# Nivel_superior.net
KiCad netlist of a schematic drawn in EAGLE
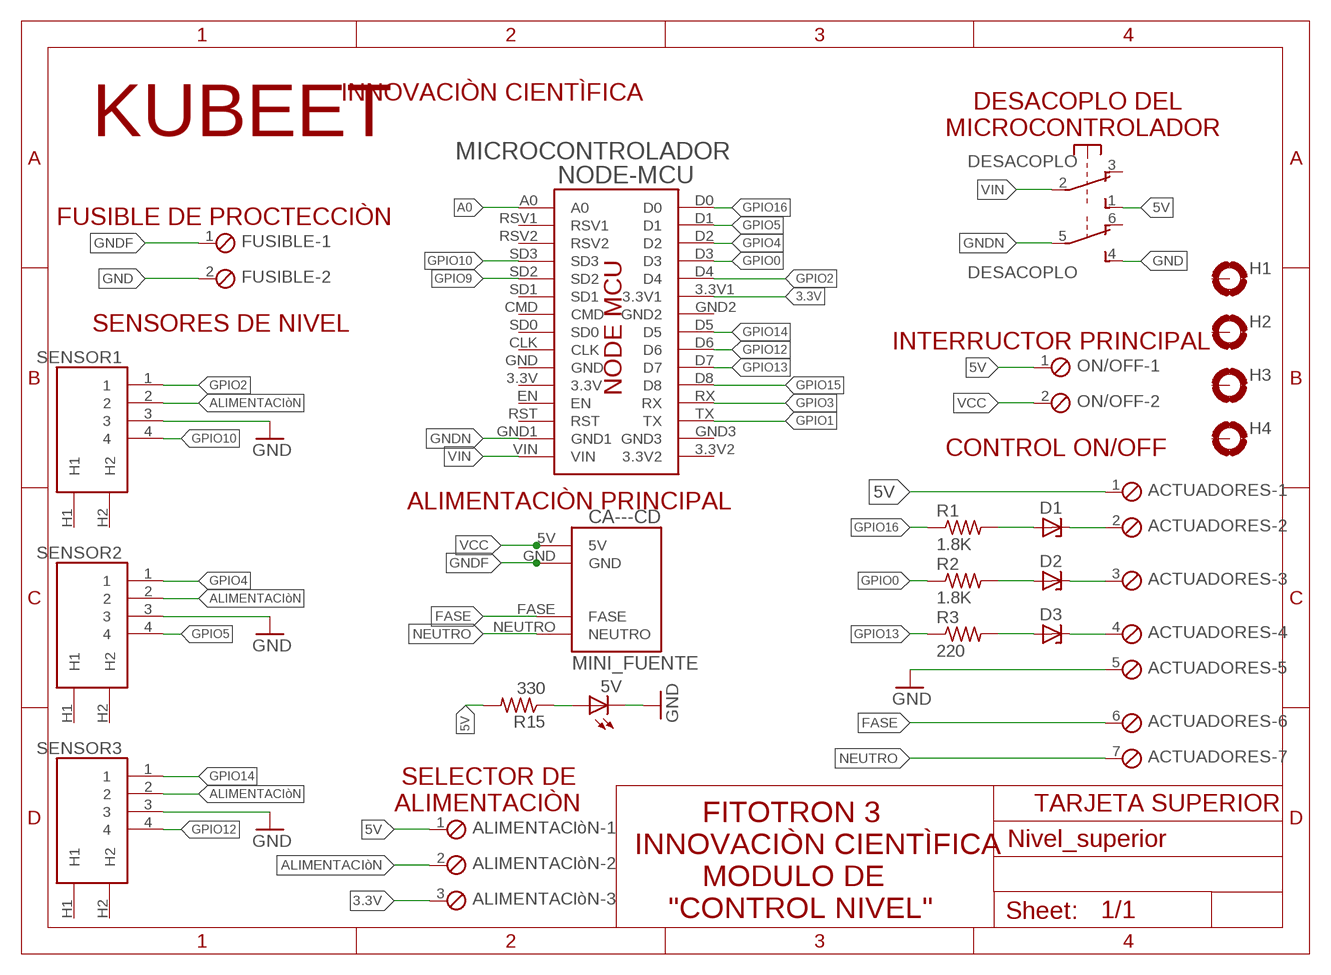
[diagram p0: schematic, sheet 1]

(export (version "E")
  (design (tool "Eeschema 10.0.6"))
  (components
    (comp (ref "5V")
      (value "LED5MM")
      (footprint "eagle-import:LED5MM")
      (libsource (lib "eagle-import") (part "LED5MM"))
    )
    (comp (ref "ACTUADORES")
      (value "MPT7")
      (footprint "eagle-import:7POL254")
      (libsource (lib "eagle-import") (part "MPT7"))
    )
    (comp (ref "ALIMENTACIòN")
      (value "MPT3")
      (footprint "eagle-import:3POL254")
      (libsource (lib "eagle-import") (part "MPT3"))
    )
    (comp (ref "CA---CD")
      (value "MINI_FUENTE")
      (footprint "eagle-import:MINI_FUENTE2")
      (libsource (lib "eagle-import") (part "MINI_FUENTE2"))
    )
    (comp (ref "D1")
      (value "1N821")
      (footprint "eagle-import:DO35Z10")
      (libsource (lib "eagle-import") (part "1N821"))
    )
    (comp (ref "D2")
      (value "1N821")
      (footprint "eagle-import:DO35Z10")
      (libsource (lib "eagle-import") (part "1N821"))
    )
    (comp (ref "D3")
      (value "1N821")
      (footprint "eagle-import:DO35Z10")
      (libsource (lib "eagle-import") (part "1N821"))
    )
    (comp (ref "DESACOPLO")
      (value "9077-2")
      (footprint "eagle-import:9077-2")
      (libsource (lib "eagle-import") (part "9077-2"))
    )
    (comp (ref "FUSIBLE")
      (value "MPT2")
      (footprint "eagle-import:2POL254")
      (libsource (lib "eagle-import") (part "MPT2"))
    )
    (comp (ref "H1")
      (value "MOUNT-PAD-ROUND3.6")
      (footprint "eagle-import:3,6-PAD")
      (libsource (lib "eagle-import") (part "MOUNT-PAD-ROUND3.6"))
    )
    (comp (ref "H2")
      (value "MOUNT-PAD-ROUND3.6")
      (footprint "eagle-import:3,6-PAD")
      (libsource (lib "eagle-import") (part "MOUNT-PAD-ROUND3.6"))
    )
    (comp (ref "H3")
      (value "MOUNT-PAD-ROUND3.6")
      (footprint "eagle-import:3,6-PAD")
      (libsource (lib "eagle-import") (part "MOUNT-PAD-ROUND3.6"))
    )
    (comp (ref "H4")
      (value "MOUNT-PAD-ROUND3.6")
      (footprint "eagle-import:3,6-PAD")
      (libsource (lib "eagle-import") (part "MOUNT-PAD-ROUND3.6"))
    )
    (comp (ref "MICROCONTROLADOR")
      (value "NODE-MCU")
      (footprint "eagle-import:NODE-MCU")
      (libsource (lib "eagle-import") (part "NODE-MCU"))
    )
    (comp (ref "ON/OFF")
      (value "MPT2")
      (footprint "eagle-import:2POL254")
      (libsource (lib "eagle-import") (part "MPT2"))
    )
    (comp (ref "R1")
      (value "1.8K")
      (footprint "eagle-import:0207_7")
      (libsource (lib "eagle-import") (part "R-US_0207/7"))
    )
    (comp (ref "R2")
      (value "1.8K")
      (footprint "eagle-import:0207_7")
      (libsource (lib "eagle-import") (part "R-US_0207/7"))
    )
    (comp (ref "R3")
      (value "220")
      (footprint "eagle-import:0207_7")
      (libsource (lib "eagle-import") (part "R-US_0207/7"))
    )
    (comp (ref "R15")
      (value "330")
      (footprint "eagle-import:0207_7")
      (libsource (lib "eagle-import") (part "R-US_0207/7"))
    )
    (comp (ref "SENSOR1")
      (value "RJ11")
      (footprint "eagle-import:RJ11")
      (libsource (lib "eagle-import") (part "RJ11"))
    )
    (comp (ref "SENSOR2")
      (value "RJ11")
      (footprint "eagle-import:RJ11")
      (libsource (lib "eagle-import") (part "RJ11"))
    )
    (comp (ref "SENSOR3")
      (value "RJ11")
      (footprint "eagle-import:RJ11")
      (libsource (lib "eagle-import") (part "RJ11"))
    )
  )
  (nets
    (net (code "1") (name "3.3V") (class "Default")
      (node (ref "ALIMENTACIòN") (pin "3") (pinfunction "1_3") (pintype "passive"))
      (node (ref "MICROCONTROLADOR") (pin "3.3V1") (pinfunction "3.3V1_3.3V1") (pintype "bidirectional"))
    )
    (net (code "2") (name "5V") (class "Default")
      (node (ref "ACTUADORES") (pin "1") (pinfunction "1_1") (pintype "passive"))
      (node (ref "ALIMENTACIòN") (pin "1") (pinfunction "1_1") (pintype "passive"))
      (node (ref "DESACOPLO") (pin "1") (pinfunction "S_1") (pintype "passive"))
      (node (ref "ON/OFF") (pin "1") (pinfunction "1_1") (pintype "passive"))
      (node (ref "R15") (pin "2") (pinfunction "2_2") (pintype "passive"))
    )
    (net (code "3") (name "A0") (class "Default")
      (node (ref "MICROCONTROLADOR") (pin "A0") (pinfunction "A0_A0") (pintype "bidirectional"))
    )
    (net (code "4") (name "ALIMENTACIòN") (class "Default")
      (node (ref "ALIMENTACIòN") (pin "2") (pinfunction "1_2") (pintype "passive"))
      (node (ref "SENSOR1") (pin "2") (pinfunction "2_2") (pintype "bidirectional"))
      (node (ref "SENSOR2") (pin "2") (pinfunction "2_2") (pintype "bidirectional"))
      (node (ref "SENSOR3") (pin "2") (pinfunction "2_2") (pintype "bidirectional"))
    )
    (net (code "5") (name "FASE") (class "Default")
      (node (ref "ACTUADORES") (pin "6") (pinfunction "1_6") (pintype "passive"))
      (node (ref "CA---CD") (pin "FASE") (pinfunction "FASE_FASE") (pintype "bidirectional"))
    )
    (net (code "6") (name "GND") (class "Default")
      (node (ref "5V") (pin "K") (pinfunction "C_K") (pintype "passive"))
      (node (ref "ACTUADORES") (pin "5") (pinfunction "1_5") (pintype "passive"))
      (node (ref "DESACOPLO") (pin "4") (pinfunction "S_4") (pintype "passive"))
      (node (ref "FUSIBLE") (pin "2") (pinfunction "1_2") (pintype "passive"))
      (node (ref "SENSOR1") (pin "3") (pinfunction "3_3") (pintype "bidirectional"))
      (node (ref "SENSOR2") (pin "3") (pinfunction "3_3") (pintype "bidirectional"))
      (node (ref "SENSOR3") (pin "3") (pinfunction "3_3") (pintype "bidirectional"))
    )
    (net (code "7") (name "GNDF") (class "Default")
      (node (ref "CA---CD") (pin "GND") (pinfunction "GND_GND") (pintype "bidirectional"))
      (node (ref "FUSIBLE") (pin "1") (pinfunction "1_1") (pintype "passive"))
    )
    (net (code "8") (name "GNDN") (class "Default")
      (node (ref "DESACOPLO") (pin "5") (pinfunction "P_5") (pintype "passive"))
      (node (ref "MICROCONTROLADOR") (pin "GND1") (pinfunction "GND1_GND1") (pintype "bidirectional"))
    )
    (net (code "9") (name "GPIO0") (class "Default")
      (node (ref "MICROCONTROLADOR") (pin "D3") (pinfunction "D3_D3") (pintype "bidirectional"))
      (node (ref "R2") (pin "1") (pinfunction "1_1") (pintype "passive"))
    )
    (net (code "10") (name "GPIO1") (class "Default")
      (node (ref "MICROCONTROLADOR") (pin "TX") (pinfunction "TX_TX") (pintype "bidirectional"))
    )
    (net (code "11") (name "GPIO2") (class "Default")
      (node (ref "MICROCONTROLADOR") (pin "D4") (pinfunction "D4_D4") (pintype "bidirectional"))
      (node (ref "SENSOR1") (pin "1") (pinfunction "1_1") (pintype "bidirectional"))
    )
    (net (code "12") (name "GPIO3") (class "Default")
      (node (ref "MICROCONTROLADOR") (pin "RX") (pinfunction "RX_RX") (pintype "bidirectional"))
    )
    (net (code "13") (name "GPIO4") (class "Default")
      (node (ref "MICROCONTROLADOR") (pin "D2") (pinfunction "D2_D2") (pintype "bidirectional"))
      (node (ref "SENSOR2") (pin "1") (pinfunction "1_1") (pintype "bidirectional"))
    )
    (net (code "14") (name "GPIO5") (class "Default")
      (node (ref "MICROCONTROLADOR") (pin "D1") (pinfunction "D1_D1") (pintype "bidirectional"))
      (node (ref "SENSOR2") (pin "4") (pinfunction "4_4") (pintype "bidirectional"))
    )
    (net (code "15") (name "GPIO9") (class "Default")
      (node (ref "MICROCONTROLADOR") (pin "SD2") (pinfunction "SD2_SD2") (pintype "bidirectional"))
    )
    (net (code "16") (name "GPIO10") (class "Default")
      (node (ref "MICROCONTROLADOR") (pin "SD3") (pinfunction "SD3_SD3") (pintype "bidirectional"))
      (node (ref "SENSOR1") (pin "4") (pinfunction "4_4") (pintype "bidirectional"))
    )
    (net (code "17") (name "GPIO12") (class "Default")
      (node (ref "MICROCONTROLADOR") (pin "D6") (pinfunction "D6_D6") (pintype "bidirectional"))
      (node (ref "SENSOR3") (pin "4") (pinfunction "4_4") (pintype "bidirectional"))
    )
    (net (code "18") (name "GPIO13") (class "Default")
      (node (ref "MICROCONTROLADOR") (pin "D7") (pinfunction "D7_D7") (pintype "bidirectional"))
      (node (ref "R3") (pin "1") (pinfunction "1_1") (pintype "passive"))
    )
    (net (code "19") (name "GPIO14") (class "Default")
      (node (ref "MICROCONTROLADOR") (pin "D5") (pinfunction "D5_D5") (pintype "bidirectional"))
      (node (ref "SENSOR3") (pin "1") (pinfunction "1_1") (pintype "bidirectional"))
    )
    (net (code "20") (name "GPIO15") (class "Default")
      (node (ref "MICROCONTROLADOR") (pin "D8") (pinfunction "D8_D8") (pintype "bidirectional"))
    )
    (net (code "21") (name "GPIO16") (class "Default")
      (node (ref "MICROCONTROLADOR") (pin "D0") (pinfunction "D0_D0") (pintype "bidirectional"))
      (node (ref "R1") (pin "1") (pinfunction "1_1") (pintype "passive"))
    )
    (net (code "22") (name "NEUTRO") (class "Default")
      (node (ref "ACTUADORES") (pin "7") (pinfunction "1_7") (pintype "passive"))
      (node (ref "CA---CD") (pin "NEUTRO") (pinfunction "NEUTRO_NEUTRO") (pintype "bidirectional"))
    )
    (net (code "23") (name "Net-(5V-PadA)") (class "Default")
      (node (ref "5V") (pin "A") (pinfunction "A_A") (pintype "passive"))
      (node (ref "R15") (pin "1") (pinfunction "1_1") (pintype "passive"))
    )
    (net (code "24") (name "Net-(ACTUADORESB-1)") (class "Default")
      (node (ref "ACTUADORES") (pin "2") (pinfunction "1_2") (pintype "passive"))
      (node (ref "D1") (pin "C") (pinfunction "C_C") (pintype "passive"))
    )
    (net (code "25") (name "Net-(ACTUADORESC-1)") (class "Default")
      (node (ref "ACTUADORES") (pin "3") (pinfunction "1_3") (pintype "passive"))
      (node (ref "D2") (pin "C") (pinfunction "C_C") (pintype "passive"))
    )
    (net (code "26") (name "Net-(ACTUADORESD-1)") (class "Default")
      (node (ref "ACTUADORES") (pin "4") (pinfunction "1_4") (pintype "passive"))
      (node (ref "D3") (pin "C") (pinfunction "C_C") (pintype "passive"))
    )
    (net (code "27") (name "Net-(D1-PadA)") (class "Default")
      (node (ref "D1") (pin "A") (pinfunction "A_A") (pintype "passive"))
      (node (ref "R1") (pin "2") (pinfunction "2_2") (pintype "passive"))
    )
    (net (code "28") (name "Net-(D2-PadA)") (class "Default")
      (node (ref "D2") (pin "A") (pinfunction "A_A") (pintype "passive"))
      (node (ref "R2") (pin "2") (pinfunction "2_2") (pintype "passive"))
    )
    (net (code "29") (name "Net-(D3-PadA)") (class "Default")
      (node (ref "D3") (pin "A") (pinfunction "A_A") (pintype "passive"))
      (node (ref "R3") (pin "2") (pinfunction "2_2") (pintype "passive"))
    )
    (net (code "30") (name "VCC") (class "Default")
      (node (ref "CA---CD") (pin "5V") (pinfunction "5V_5V") (pintype "bidirectional"))
      (node (ref "ON/OFF") (pin "2") (pinfunction "1_2") (pintype "passive"))
    )
    (net (code "31") (name "VIN") (class "Default")
      (node (ref "DESACOPLO") (pin "2") (pinfunction "P_2") (pintype "passive"))
      (node (ref "MICROCONTROLADOR") (pin "VIN") (pinfunction "VIN_VIN") (pintype "bidirectional"))
    )
    (net (code "32") (name "unconnected-(DESACOPLOA-O-Pad3)") (class "Default")
      (node (ref "DESACOPLO") (pin "3") (pinfunction "O_3") (pintype "passive"))
    )
    (net (code "33") (name "unconnected-(DESACOPLOB-O-Pad6)") (class "Default")
      (node (ref "DESACOPLO") (pin "6") (pinfunction "O_6") (pintype "passive"))
    )
    (net (code "34") (name "unconnected-(H1-MOUNT-PadB3,6)") (class "Default")
      (node (ref "H1") (pin "B3,6") (pinfunction "MOUNT_B3,6") (pintype "passive"))
    )
    (net (code "35") (name "unconnected-(H2-MOUNT-PadB3,6)") (class "Default")
      (node (ref "H2") (pin "B3,6") (pinfunction "MOUNT_B3,6") (pintype "passive"))
    )
    (net (code "36") (name "unconnected-(H3-MOUNT-PadB3,6)") (class "Default")
      (node (ref "H3") (pin "B3,6") (pinfunction "MOUNT_B3,6") (pintype "passive"))
    )
    (net (code "37") (name "unconnected-(H4-MOUNT-PadB3,6)") (class "Default")
      (node (ref "H4") (pin "B3,6") (pinfunction "MOUNT_B3,6") (pintype "passive"))
    )
    (net (code "38") (name "unconnected-(MICROCONTROLADOR-Pad3.3V)") (class "Default")
      (node (ref "MICROCONTROLADOR") (pin "3.3V") (pinfunction "3.3V_3.3V") (pintype "bidirectional"))
    )
    (net (code "39") (name "unconnected-(MICROCONTROLADOR-Pad3.3V2)") (class "Default")
      (node (ref "MICROCONTROLADOR") (pin "3.3V2") (pinfunction "3.3V2_3.3V2") (pintype "bidirectional"))
    )
    (net (code "40") (name "unconnected-(MICROCONTROLADOR-PadCLK)") (class "Default")
      (node (ref "MICROCONTROLADOR") (pin "CLK") (pinfunction "CLK_CLK") (pintype "bidirectional"))
    )
    (net (code "41") (name "unconnected-(MICROCONTROLADOR-PadCMD)") (class "Default")
      (node (ref "MICROCONTROLADOR") (pin "CMD") (pinfunction "CMD_CMD") (pintype "bidirectional"))
    )
    (net (code "42") (name "unconnected-(MICROCONTROLADOR-PadEN)") (class "Default")
      (node (ref "MICROCONTROLADOR") (pin "EN") (pinfunction "EN_EN") (pintype "bidirectional"))
    )
    (net (code "43") (name "unconnected-(MICROCONTROLADOR-PadGND)") (class "Default")
      (node (ref "MICROCONTROLADOR") (pin "GND") (pinfunction "GND_GND") (pintype "bidirectional"))
    )
    (net (code "44") (name "unconnected-(MICROCONTROLADOR-PadGND2)") (class "Default")
      (node (ref "MICROCONTROLADOR") (pin "GND2") (pinfunction "GND2_GND2") (pintype "bidirectional"))
    )
    (net (code "45") (name "unconnected-(MICROCONTROLADOR-PadGND3)") (class "Default")
      (node (ref "MICROCONTROLADOR") (pin "GND3") (pinfunction "GND3_GND3") (pintype "bidirectional"))
    )
    (net (code "46") (name "unconnected-(MICROCONTROLADOR-PadRST)") (class "Default")
      (node (ref "MICROCONTROLADOR") (pin "RST") (pinfunction "RST_RST") (pintype "bidirectional"))
    )
    (net (code "47") (name "unconnected-(MICROCONTROLADOR-PadRSV1)") (class "Default")
      (node (ref "MICROCONTROLADOR") (pin "RSV1") (pinfunction "RSV1_RSV1") (pintype "bidirectional"))
    )
    (net (code "48") (name "unconnected-(MICROCONTROLADOR-PadRSV2)") (class "Default")
      (node (ref "MICROCONTROLADOR") (pin "RSV2") (pinfunction "RSV2_RSV2") (pintype "bidirectional"))
    )
    (net (code "49") (name "unconnected-(MICROCONTROLADOR-PadSD0)") (class "Default")
      (node (ref "MICROCONTROLADOR") (pin "SD0") (pinfunction "SD0_SD0") (pintype "bidirectional"))
    )
    (net (code "50") (name "unconnected-(MICROCONTROLADOR-PadSD1)") (class "Default")
      (node (ref "MICROCONTROLADOR") (pin "SD1") (pinfunction "SD1_SD1") (pintype "bidirectional"))
    )
    (net (code "51") (name "unconnected-(SENSOR1-PadH1)") (class "Default")
      (node (ref "SENSOR1") (pin "H1") (pinfunction "H1_H1") (pintype "bidirectional"))
    )
    (net (code "52") (name "unconnected-(SENSOR1-PadH2)") (class "Default")
      (node (ref "SENSOR1") (pin "H2") (pinfunction "H2_H2") (pintype "bidirectional"))
    )
    (net (code "53") (name "unconnected-(SENSOR2-PadH1)") (class "Default")
      (node (ref "SENSOR2") (pin "H1") (pinfunction "H1_H1") (pintype "bidirectional"))
    )
    (net (code "54") (name "unconnected-(SENSOR2-PadH2)") (class "Default")
      (node (ref "SENSOR2") (pin "H2") (pinfunction "H2_H2") (pintype "bidirectional"))
    )
    (net (code "55") (name "unconnected-(SENSOR3-PadH1)") (class "Default")
      (node (ref "SENSOR3") (pin "H1") (pinfunction "H1_H1") (pintype "bidirectional"))
    )
    (net (code "56") (name "unconnected-(SENSOR3-PadH2)") (class "Default")
      (node (ref "SENSOR3") (pin "H2") (pinfunction "H2_H2") (pintype "bidirectional"))
    )
  )
)
